# nRF9160.net
KiCad netlist of a schematic drawn in Altium Designer
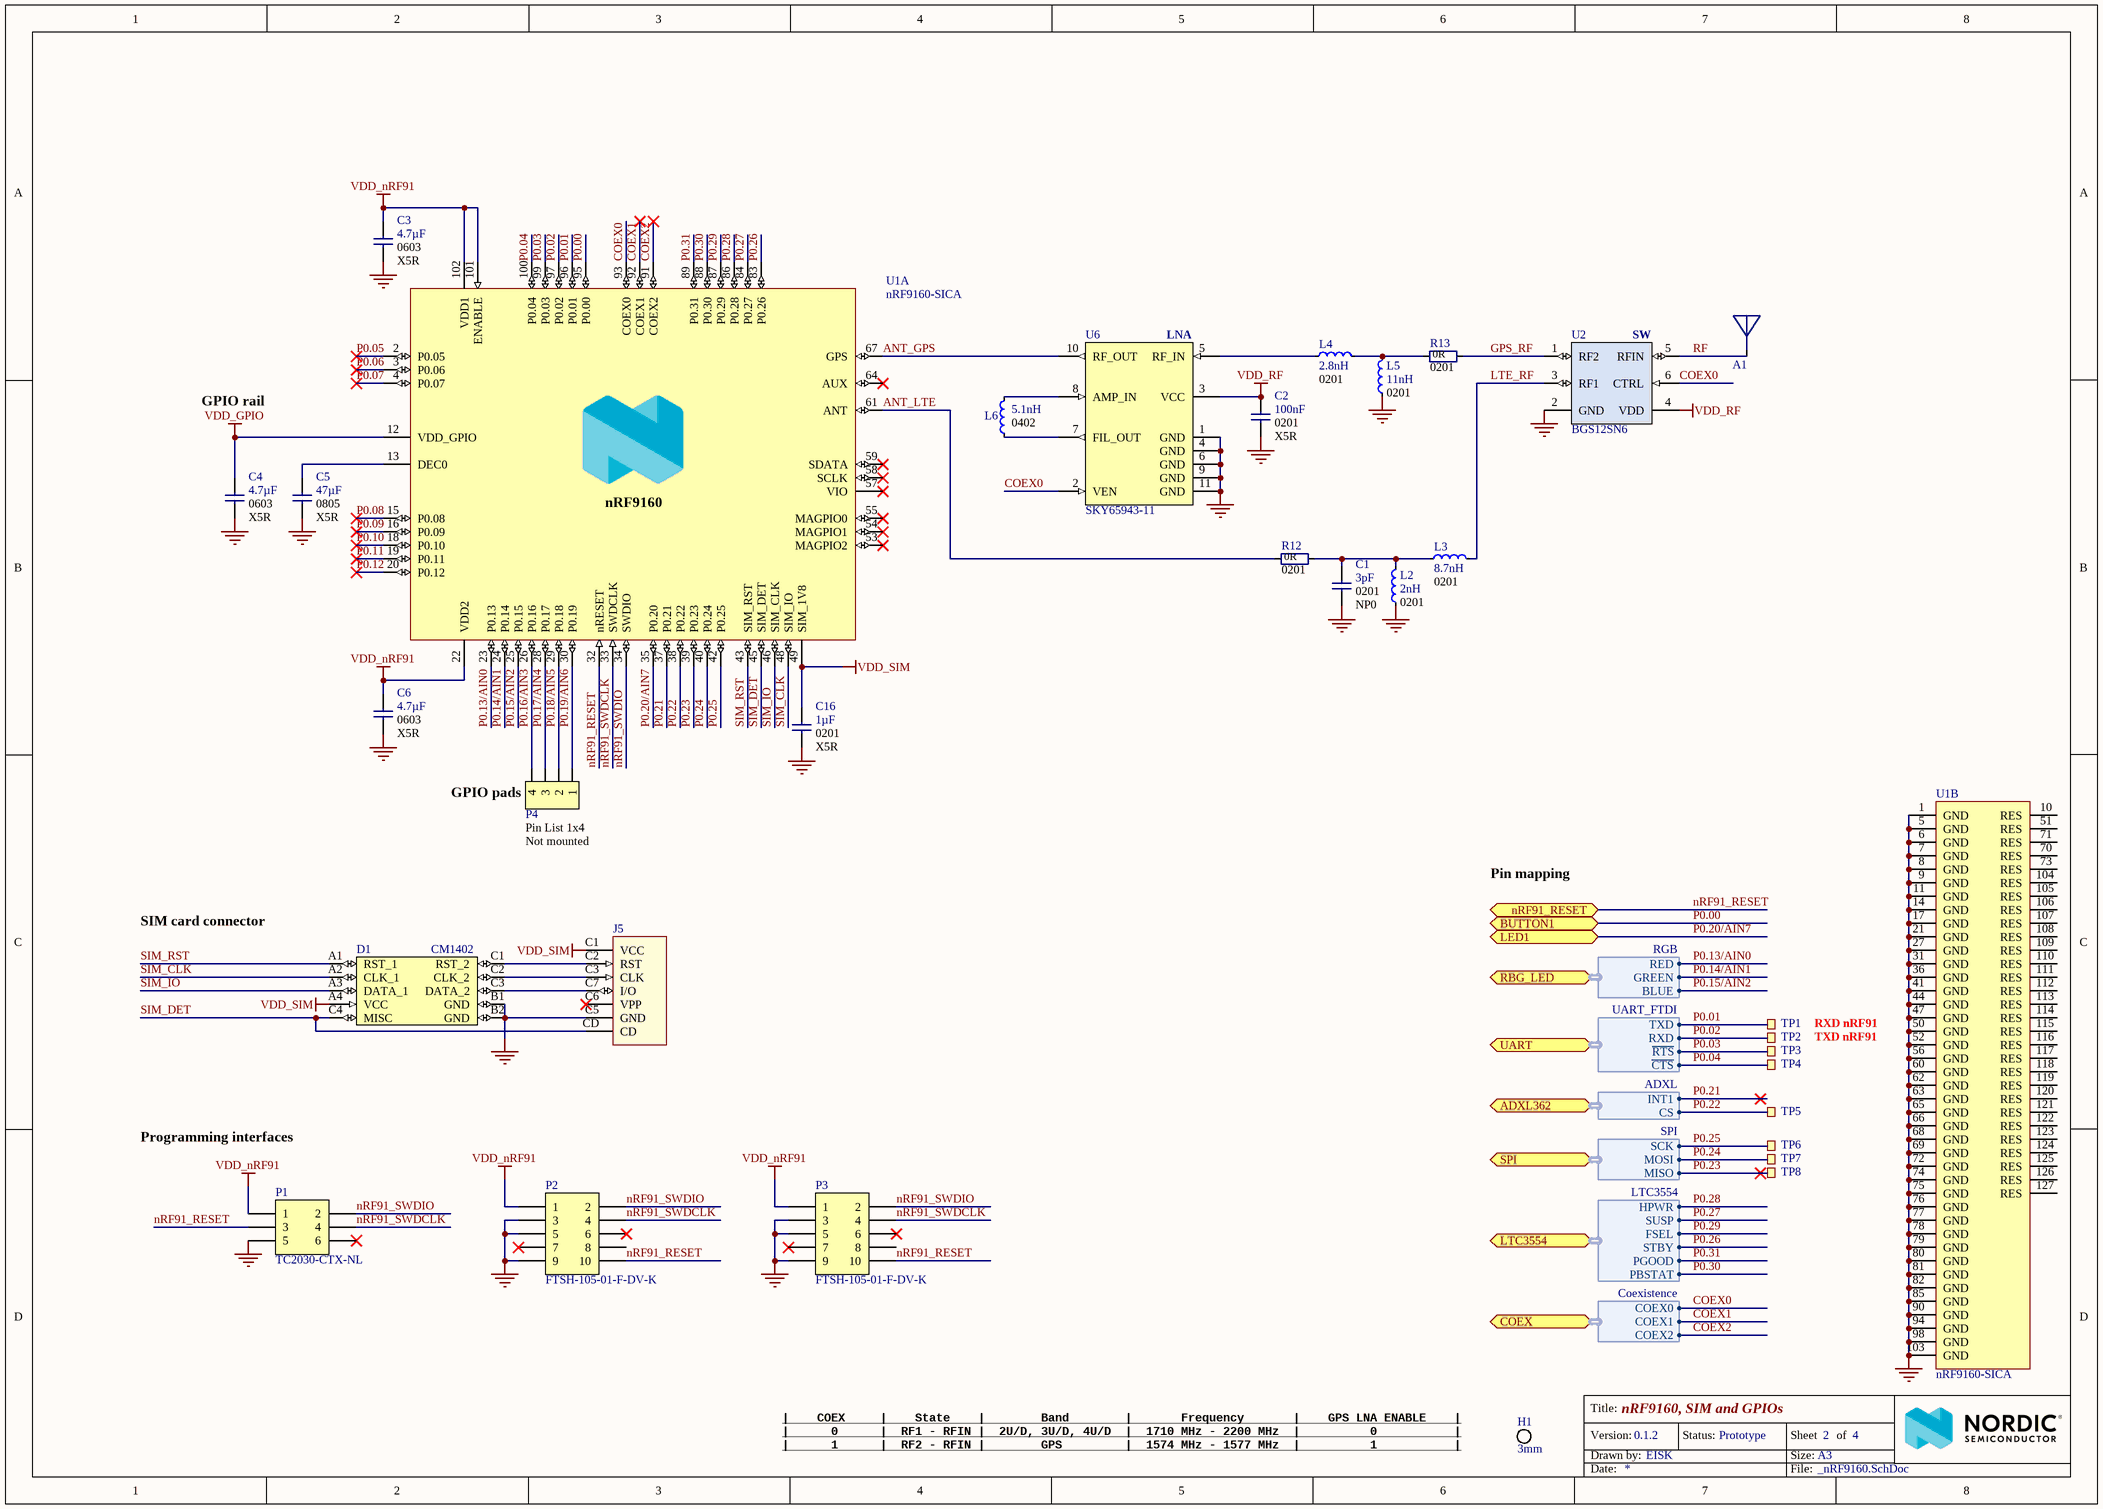
[diagram p0: _nRF9160.SchDoc]

(export (version "E")
  (design (tool "Eeschema 10.0.6"))
  (components
    (comp (ref "A1")
      (value "FR01-S4-250")
      (footprint "FRACTUS_CUBE_mXTEND")
      (description "CUBE mXTEND Antenna Booster (GSM, UMTS, LTE)")
      (fields (field (name "MANUFACTURER") "Fractus Antennas S.L."))
      (libsource (lib "_components") (part "ANT{colon}CUBE_mXTEND"))
    )
    (comp (ref "C1")
      (value "3pF")
      (footprint "CAPC0603X03L_C")
      (description "Capacitor, NP0, ±10%, 10V")
      (fields
        (field (name "FOOTPRINT DOC") "0201")
        (field (name "TEMPCOEFF") "NP0")
        (field (name "PUBLISHER") "Nordic Semiconductor")
      )
      (libsource (lib "_components") (part "CAP{colon}0201"))
    )
    (comp (ref "C2")
      (value "100nF")
      (footprint "CAPC0603X03L_C")
      (description "Capacitor, X5R, ±10%, 10V")
      (fields
        (field (name "FOOTPRINT DOC") "0201")
        (field (name "TEMPCOEFF") "X5R")
        (field (name "PUBLISHER") "Nordic Semiconductor")
      )
      (libsource (lib "_components") (part "CAP{colon}0201"))
    )
    (comp (ref "C3")
      (value "4.7µF")
      (footprint "CAPC1608X06L")
      (description "Capacitor, X5R, ±10%, 6.3V")
      (fields
        (field (name "FOOTPRINT DOC") "0603")
        (field (name "TEMPCOEFF") "X5R")
        (field (name "PUBLISHER") "Nordic Semiconductor")
      )
      (libsource (lib "_components") (part "CAP{colon}0603"))
    )
    (comp (ref "C4")
      (value "4.7µF")
      (footprint "CAPC1608X06L")
      (description "Capacitor, X5R, ±10%, 6.3V")
      (fields
        (field (name "FOOTPRINT DOC") "0603")
        (field (name "TEMPCOEFF") "X5R")
        (field (name "PUBLISHER") "Nordic Semiconductor")
      )
      (libsource (lib "_components") (part "CAP{colon}0603"))
    )
    (comp (ref "C5")
      (value "47µF")
      (footprint "CAPC2012X11L")
      (description "Capacitor, X5R, ±20%, 6.3V")
      (fields
        (field (name "FOOTPRINT DOC") "0805")
        (field (name "TEMPCOEFF") "X5R")
        (field (name "PUBLISHER") "Nordic Semiconductor")
      )
      (libsource (lib "_components") (part "CAP{colon}0805"))
    )
    (comp (ref "C6")
      (value "4.7µF")
      (footprint "CAPC1608X06L")
      (description "Capacitor, X5R, ±10%, 6.3V")
      (fields
        (field (name "FOOTPRINT DOC") "0603")
        (field (name "TEMPCOEFF") "X5R")
        (field (name "PUBLISHER") "Nordic Semiconductor")
      )
      (libsource (lib "_components") (part "CAP{colon}0603"))
    )
    (comp (ref "C16")
      (value "1µF")
      (footprint "CAPC0603X03L_C")
      (description "Capacitor, X5R, ±10%, 10V")
      (fields
        (field (name "FOOTPRINT DOC") "0201")
        (field (name "TEMPCOEFF") "X5R")
        (field (name "PUBLISHER") "Nordic Semiconductor")
      )
      (libsource (lib "_components") (part "CAP{colon}0201"))
    )
    (comp (ref "D1")
      (value "CM1402")
      (footprint "CM1402")
      (description "EMI Network Filter Arrays SIM CARD EMI FILTER WITH ESD PROTECTION")
      (fields
        (field (name "MANUFACTURER") "ON Semiconductor")
        (field (name "MANUFACTURER PART NUMBER") "CM1402-03CP")
        (field (name "PUBLISHER") "Nordic Semiconductor")
      )
      (libsource (lib "_components") (part "CM1402"))
    )
    (comp (ref "H1")
      (value "3mm")
      (footprint "HOLE_NP_3MM")
      (libsource (lib "_components") (part "HOLE{colon}M3"))
    )
    (comp (ref "J5")
      (value "SIM8055-6-1-14-00-A_revA1")
      (footprint "GCT_SIM8055-6-1-14-00-A_revA1")
      (description "Nano SIM Card Connector, Push-Pull Type, 6 Pin, SMT, Profile 1.35mm")
      (fields
        (field (name "MANUFACTURER PART NUMBER") "SIM8055-6-1-14-00-A")
        (field (name "MANUFACTURER") "GCT")
      )
      (libsource (lib "_components") (part "SIM8055-6-1-14-00-A_revA1"))
    )
    (comp (ref "L2")
      (value "2nH")
      (footprint "INDC0603X03L_C")
      (description "Inductor, 350mA, ±3%")
      (fields
        (field (name "MANUFACTURER") "Murata")
        (field (name "FOOTPRINT DOC") "0201")
        (field (name "PUBLISHER") "Nordic Semiconductor")
      )
      (libsource (lib "_components") (part "IND{colon}0201"))
    )
    (comp (ref "L3")
      (value "8.7nH")
      (footprint "INDC0603X03L_C")
      (description "Inductor, 350mA, ±3%")
      (fields
        (field (name "MANUFACTURER") "Murata")
        (field (name "FOOTPRINT DOC") "0201")
        (field (name "PUBLISHER") "Nordic Semiconductor")
      )
      (libsource (lib "_components") (part "IND{colon}0201"))
    )
    (comp (ref "L4")
      (value "2.8nH")
      (footprint "INDC0603X03L_C")
      (description "Inductor, 350mA, ±3%")
      (fields
        (field (name "MANUFACTURER") "Murata")
        (field (name "FOOTPRINT DOC") "0201")
        (field (name "PUBLISHER") "Nordic Semiconductor")
      )
      (libsource (lib "_components") (part "IND{colon}0201"))
    )
    (comp (ref "L5")
      (value "11nH")
      (footprint "INDC0603X03L_C")
      (description "Inductor, 350mA, ±3%")
      (fields
        (field (name "MANUFACTURER") "Murata")
        (field (name "FOOTPRINT DOC") "0201")
        (field (name "PUBLISHER") "Nordic Semiconductor")
      )
      (libsource (lib "_components") (part "IND{colon}0201"))
    )
    (comp (ref "L6")
      (value "5.1nH")
      (footprint "INDC1005X04L_WW")
      (description "Inductor, 600mA, ±0.1nH, 120mΩ, Q=25")
      (fields
        (field (name "PART NUMBER") "L0402-5n1-Wirewound-Murata")
        (field (name "MANUFACTURER") "Murata")
        (field (name "FOOTPRINT DOC") "0402")
        (field (name "PUBLISHER") "Nordic Semiconductor")
      )
      (libsource (lib "_components") (part "IND{colon}Murata"))
    )
    (comp (ref "P1")
      (value "TC2030-CTX-NL")
      (footprint "TC2030-IDC-NLFP")
      (description "CBL PLUG-OF-NAILS 6-PIN")
      (fields
        (field (name "MANUFACTURER") "Tag-Connect LLC")
        (field (name "PUBLISHER") "Nordic Semiconductor")
      )
      (libsource (lib "_components") (part "CONN-2x3_No_BOM"))
    )
    (comp (ref "P2")
      (value "FTSH-105-01-F-DV-K")
      (footprint "HDR_2x5-SMD-1.27mm")
      (description "Connector Header Surface Mount 10 position 0.050\" (1.27mm)")
      (fields (field (name "MANUFACTURER") "Samtec Inc.") (field (name "PUBLISHER") "Nordic Semiconductor"))
      (libsource (lib "_components") (part "Header 2x5 No-BOM"))
    )
    (comp (ref "P3")
      (value "FTSH-105-01-F-DV-K")
      (footprint "HDR_2x5-SMD-1.27mm-K")
      (description "Connector Header Surface Mount 10 position 0.050\" (1.27mm)")
      (fields (field (name "MANUFACTURER") "Samtec Inc.") (field (name "PUBLISHER") "Nordic Semiconductor"))
      (libsource (lib "_components") (part "Header 2x5 Shielded SMD"))
    )
    (comp (ref "P4")
      (value "Pin List 1x4")
      (footprint "LIST_1x4-NC")
      (description "Pin List 1x4, 2.54mm (100mil)")
      (fields (field (name "ASSEMBLY") "Not mounted") (field (name "PUBLISHER") "Nordic Semiconductor"))
      (libsource (lib "_components") (part "CONN-4"))
    )
    (comp (ref "R12")
      (value "0R")
      (footprint "RESC0603X03L_C")
      (fields (field (name "FOOTPRINT DOC") "0201") (field (name "PUBLISHER") "Nordic Semiconductor"))
      (libsource (lib "_components") (part "RES{colon}0201"))
    )
    (comp (ref "R13")
      (value "0R")
      (footprint "RESC0603X03L_C")
      (fields (field (name "FOOTPRINT DOC") "0201") (field (name "PUBLISHER") "Nordic Semiconductor"))
      (libsource (lib "_components") (part "RES{colon}0201"))
    )
    (comp (ref "TP1")
      (value "Ø1.0mm,SMD")
      (footprint "TP_SMD_Ø1.0mm")
      (description "1.0mm circular SMD testpad")
      (fields
        (field (name "MANUFACTURER") "Nordic Semiconductor")
        (field (name "PUBLISHER") "Nordic Semiconductor")
      )
      (libsource (lib "_components") (part "TESTPAD"))
    )
    (comp (ref "TP2")
      (value "Ø1.0mm,SMD")
      (footprint "TP_SMD_Ø1.0mm")
      (description "1.0mm circular SMD testpad")
      (fields
        (field (name "MANUFACTURER") "Nordic Semiconductor")
        (field (name "PUBLISHER") "Nordic Semiconductor")
      )
      (libsource (lib "_components") (part "TESTPAD"))
    )
    (comp (ref "TP3")
      (value "Ø1.0mm,SMD")
      (footprint "TP_SMD_Ø1.0mm")
      (description "1.0mm circular SMD testpad")
      (fields
        (field (name "MANUFACTURER") "Nordic Semiconductor")
        (field (name "PUBLISHER") "Nordic Semiconductor")
      )
      (libsource (lib "_components") (part "TESTPAD"))
    )
    (comp (ref "TP4")
      (value "Ø1.0mm,SMD")
      (footprint "TP_SMD_Ø1.0mm")
      (description "1.0mm circular SMD testpad")
      (fields
        (field (name "MANUFACTURER") "Nordic Semiconductor")
        (field (name "PUBLISHER") "Nordic Semiconductor")
      )
      (libsource (lib "_components") (part "TESTPAD"))
    )
    (comp (ref "TP5")
      (value "Ø1.0mm,SMD")
      (footprint "TP_SMD_Ø1.0mm")
      (description "1.0mm circular SMD testpad")
      (fields
        (field (name "MANUFACTURER") "Nordic Semiconductor")
        (field (name "PUBLISHER") "Nordic Semiconductor")
      )
      (libsource (lib "_components") (part "TESTPAD"))
    )
    (comp (ref "TP6")
      (value "Ø1.0mm,SMD")
      (footprint "TP_SMD_Ø1.0mm")
      (description "1.0mm circular SMD testpad")
      (fields
        (field (name "MANUFACTURER") "Nordic Semiconductor")
        (field (name "PUBLISHER") "Nordic Semiconductor")
      )
      (libsource (lib "_components") (part "TESTPAD"))
    )
    (comp (ref "TP7")
      (value "Ø1.0mm,SMD")
      (footprint "TP_SMD_Ø1.0mm")
      (description "1.0mm circular SMD testpad")
      (fields
        (field (name "MANUFACTURER") "Nordic Semiconductor")
        (field (name "PUBLISHER") "Nordic Semiconductor")
      )
      (libsource (lib "_components") (part "TESTPAD"))
    )
    (comp (ref "TP8")
      (value "Ø1.0mm,SMD")
      (footprint "TP_SMD_Ø1.0mm")
      (description "1.0mm circular SMD testpad")
      (fields
        (field (name "MANUFACTURER") "Nordic Semiconductor")
        (field (name "PUBLISHER") "Nordic Semiconductor")
      )
      (libsource (lib "_components") (part "TESTPAD"))
    )
    (comp (ref "U1")
      (value "nRF9160-SICA")
      (footprint "LGA50P1600X1050X104-161N")
      (description "Low power System-in-Package with integrated LTE-M/NB-IoT modem and GPS")
      (fields
        (field (name "MANUFACTURER") "Nordic Semiconductor")
        (field (name "PUBLISHER") "Nordic Semiconductor")
      )
      (libsource (lib "_components") (part "nRF9160_SICA"))
    )
    (comp (ref "U2")
      (value "BGS12SN6")
      (footprint "PG-TSNP-6-2")
      (description "Wideband RF SPDT Switch")
      (fields (field (name "MANUFACTURER") "Infineon Technologies"))
      (libsource (lib "_components") (part "BGS12SN6"))
    )
    (comp (ref "U6")
      (value "SKY65943-11")
      (footprint "SKY6594311")
      (description "GNSS Low-Noise Amplifier Front-End Module with Integrated Pre-Filter and Post-Filter")
      (fields (field (name "MANUFACTURER") "Skyworks") (field (name "PUBLISHER") "Nordic Semiconductor"))
      (libsource (lib "_components") (part "SKY65943-11"))
    )
  )
  (nets
    (net (code "7") (name "/ANT_GPS") (class "Default")
      (node (ref "U1") (pin "67") (pinfunction "GPS_67") (pintype "bidirectional"))
      (node (ref "U6") (pin "10") (pinfunction "RF_OUT_10") (pintype "output"))
    )
    (net (code "8") (name "/ANT_LTE") (class "Default")
      (node (ref "R12") (pin "1") (pinfunction "1_1") (pintype "passive"))
      (node (ref "U1") (pin "61") (pinfunction "ANT_61") (pintype "bidirectional"))
    )
    (net (code "9") (name "/COEX0") (class "Default")
      (node (ref "U1") (pin "93") (pinfunction "COEX0_93") (pintype "bidirectional"))
      (node (ref "U2") (pin "6") (pinfunction "CTRL_6") (pintype "input"))
      (node (ref "U6") (pin "2") (pinfunction "VEN_2") (pintype "input"))
    )
    (net (code "10") (name "/COEX1") (class "Default")
      (node (ref "U1") (pin "92") (pinfunction "COEX1_92") (pintype "bidirectional+no_connect"))
    )
    (net (code "11") (name "/COEX2") (class "Default")
      (node (ref "U1") (pin "91") (pinfunction "COEX2_91") (pintype "bidirectional+no_connect"))
    )
    (net (code "12") (name "/GPS_RF") (class "Default")
      (node (ref "R13") (pin "2") (pinfunction "2_2") (pintype "passive"))
      (node (ref "U2") (pin "1") (pinfunction "RF2_1") (pintype "bidirectional"))
    )
    (net (code "13") (name "/LTE_RF") (class "Default")
      (node (ref "L3") (pin "2") (pinfunction "2_2") (pintype "passive"))
      (node (ref "U2") (pin "3") (pinfunction "RF1_3") (pintype "bidirectional"))
    )
    (net (code "14") (name "/P0.00") (class "Default")
      (node (ref "U1") (pin "95") (pinfunction "P0.00_95") (pintype "bidirectional"))
    )
    (net (code "15") (name "/P0.01") (class "Default")
      (node (ref "TP1") (pin "1") (pinfunction "1_1") (pintype "passive"))
      (node (ref "U1") (pin "96") (pinfunction "P0.01_96") (pintype "bidirectional"))
    )
    (net (code "16") (name "/P0.02") (class "Default")
      (node (ref "TP2") (pin "1") (pinfunction "1_1") (pintype "passive"))
      (node (ref "U1") (pin "97") (pinfunction "P0.02_97") (pintype "bidirectional"))
    )
    (net (code "17") (name "/P0.03") (class "Default")
      (node (ref "TP3") (pin "1") (pinfunction "1_1") (pintype "passive"))
      (node (ref "U1") (pin "99") (pinfunction "P0.03_99") (pintype "bidirectional"))
    )
    (net (code "18") (name "/P0.04") (class "Default")
      (node (ref "TP4") (pin "1") (pinfunction "1_1") (pintype "passive"))
      (node (ref "U1") (pin "100") (pinfunction "P0.04_100") (pintype "bidirectional"))
    )
    (net (code "19") (name "/P0.05") (class "Default")
      (node (ref "U1") (pin "2") (pinfunction "P0.05_2") (pintype "bidirectional+no_connect"))
    )
    (net (code "20") (name "/P0.06") (class "Default")
      (node (ref "U1") (pin "3") (pinfunction "P0.06_3") (pintype "bidirectional+no_connect"))
    )
    (net (code "21") (name "/P0.07") (class "Default")
      (node (ref "U1") (pin "4") (pinfunction "P0.07_4") (pintype "bidirectional+no_connect"))
    )
    (net (code "22") (name "/P0.08") (class "Default")
      (node (ref "U1") (pin "15") (pinfunction "P0.08_15") (pintype "bidirectional+no_connect"))
    )
    (net (code "23") (name "/P0.09") (class "Default")
      (node (ref "U1") (pin "16") (pinfunction "P0.09_16") (pintype "bidirectional+no_connect"))
    )
    (net (code "24") (name "/P0.10") (class "Default")
      (node (ref "U1") (pin "18") (pinfunction "P0.10_18") (pintype "bidirectional+no_connect"))
    )
    (net (code "25") (name "/P0.11") (class "Default")
      (node (ref "U1") (pin "19") (pinfunction "P0.11_19") (pintype "bidirectional+no_connect"))
    )
    (net (code "26") (name "/P0.12") (class "Default")
      (node (ref "U1") (pin "20") (pinfunction "P0.12_20") (pintype "bidirectional+no_connect"))
    )
    (net (code "27") (name "/P0.13{slash}AIN0") (class "Default")
      (node (ref "U1") (pin "23") (pinfunction "P0.13_23") (pintype "bidirectional"))
    )
    (net (code "28") (name "/P0.14{slash}AIN1") (class "Default")
      (node (ref "U1") (pin "24") (pinfunction "P0.14_24") (pintype "bidirectional"))
    )
    (net (code "29") (name "/P0.15{slash}AIN2") (class "Default")
      (node (ref "U1") (pin "25") (pinfunction "P0.15_25") (pintype "bidirectional"))
    )
    (net (code "30") (name "/P0.16{slash}AIN3") (class "Default")
      (node (ref "P4") (pin "4") (pinfunction "4_4") (pintype "passive"))
      (node (ref "U1") (pin "26") (pinfunction "P0.16_26") (pintype "bidirectional"))
    )
    (net (code "31") (name "/P0.17{slash}AIN4") (class "Default")
      (node (ref "P4") (pin "3") (pinfunction "3_3") (pintype "passive"))
      (node (ref "U1") (pin "28") (pinfunction "P0.17_28") (pintype "bidirectional"))
    )
    (net (code "32") (name "/P0.18{slash}AIN5") (class "Default")
      (node (ref "P4") (pin "2") (pinfunction "2_2") (pintype "passive"))
      (node (ref "U1") (pin "29") (pinfunction "P0.18_29") (pintype "bidirectional"))
    )
    (net (code "33") (name "/P0.19{slash}AIN6") (class "Default")
      (node (ref "P4") (pin "1") (pinfunction "1_1") (pintype "passive"))
      (node (ref "U1") (pin "30") (pinfunction "P0.19_30") (pintype "bidirectional"))
    )
    (net (code "34") (name "/P0.20{slash}AIN7") (class "Default")
      (node (ref "U1") (pin "35") (pinfunction "P0.20_35") (pintype "bidirectional"))
    )
    (net (code "35") (name "/P0.21") (class "Default")
      (node (ref "U1") (pin "37") (pinfunction "P0.21_37") (pintype "bidirectional"))
    )
    (net (code "36") (name "/P0.22") (class "Default")
      (node (ref "TP5") (pin "1") (pinfunction "1_1") (pintype "passive"))
      (node (ref "U1") (pin "38") (pinfunction "P0.22_38") (pintype "bidirectional"))
    )
    (net (code "37") (name "/P0.23") (class "Default")
      (node (ref "TP8") (pin "1") (pinfunction "1_1") (pintype "passive"))
      (node (ref "U1") (pin "39") (pinfunction "P0.23_39") (pintype "bidirectional"))
    )
    (net (code "38") (name "/P0.24") (class "Default")
      (node (ref "TP7") (pin "1") (pinfunction "1_1") (pintype "passive"))
      (node (ref "U1") (pin "40") (pinfunction "P0.24_40") (pintype "bidirectional"))
    )
    (net (code "39") (name "/P0.25") (class "Default")
      (node (ref "TP6") (pin "1") (pinfunction "1_1") (pintype "passive"))
      (node (ref "U1") (pin "42") (pinfunction "P0.25_42") (pintype "bidirectional"))
    )
    (net (code "40") (name "/P0.26") (class "Default")
      (node (ref "U1") (pin "83") (pinfunction "P0.26_83") (pintype "bidirectional"))
    )
    (net (code "41") (name "/P0.27") (class "Default")
      (node (ref "U1") (pin "84") (pinfunction "P0.27_84") (pintype "bidirectional"))
    )
    (net (code "42") (name "/P0.28") (class "Default")
      (node (ref "U1") (pin "86") (pinfunction "P0.28_86") (pintype "bidirectional"))
    )
    (net (code "43") (name "/P0.29") (class "Default")
      (node (ref "U1") (pin "87") (pinfunction "P0.29_87") (pintype "bidirectional"))
    )
    (net (code "44") (name "/P0.30") (class "Default")
      (node (ref "U1") (pin "88") (pinfunction "P0.30_88") (pintype "bidirectional"))
    )
    (net (code "45") (name "/P0.31") (class "Default")
      (node (ref "U1") (pin "89") (pinfunction "P0.31_89") (pintype "bidirectional"))
    )
    (net (code "46") (name "/RF") (class "Default")
      (node (ref "A1") (pin "1") (pinfunction "1_1") (pintype "passive"))
      (node (ref "U2") (pin "5") (pinfunction "RFIN_5") (pintype "bidirectional"))
    )
    (net (code "47") (name "/SIM_CLK") (class "Default")
      (node (ref "D1") (pin "A2") (pinfunction "CLK_1_A2") (pintype "bidirectional"))
      (node (ref "U1") (pin "48") (pinfunction "SIM_IO_48") (pintype "bidirectional"))
    )
    (net (code "48") (name "/SIM_DET") (class "Default")
      (node (ref "D1") (pin "C4") (pinfunction "MISC_C4") (pintype "bidirectional"))
      (node (ref "J5") (pin "CD") (pinfunction "CD_CD") (pintype "passive"))
      (node (ref "U1") (pin "45") (pinfunction "SIM_DET_45") (pintype "bidirectional"))
    )
    (net (code "49") (name "/SIM_IO") (class "Default")
      (node (ref "D1") (pin "A3") (pinfunction "DATA_1_A3") (pintype "bidirectional"))
      (node (ref "U1") (pin "46") (pinfunction "SIM_CLK_46") (pintype "bidirectional"))
    )
    (net (code "50") (name "/SIM_RST") (class "Default")
      (node (ref "D1") (pin "A1") (pinfunction "RST_1_A1") (pintype "bidirectional"))
      (node (ref "U1") (pin "43") (pinfunction "SIM_RST_43") (pintype "bidirectional"))
    )
    (net (code "51") (name "/nRF91_RESET") (class "Default")
      (node (ref "P1") (pin "3") (pinfunction "3_3") (pintype "passive"))
      (node (ref "P2") (pin "10") (pinfunction "10_10") (pintype "passive"))
      (node (ref "P3") (pin "10") (pinfunction "10_10") (pintype "passive"))
      (node (ref "U1") (pin "32") (pinfunction "nRESET_32") (pintype "input"))
    )
    (net (code "52") (name "/nRF91_SWDCLK") (class "Default")
      (node (ref "P1") (pin "4") (pinfunction "4_4") (pintype "passive"))
      (node (ref "P2") (pin "4") (pinfunction "4_4") (pintype "passive"))
      (node (ref "P3") (pin "4") (pinfunction "4_4") (pintype "passive"))
      (node (ref "U1") (pin "33") (pinfunction "SWDCLK_33") (pintype "input"))
    )
    (net (code "53") (name "/nRF91_SWDIO") (class "Default")
      (node (ref "P1") (pin "2") (pinfunction "2_2") (pintype "passive"))
      (node (ref "P2") (pin "2") (pinfunction "2_2") (pintype "passive"))
      (node (ref "P3") (pin "2") (pinfunction "2_2") (pintype "passive"))
      (node (ref "U1") (pin "34") (pinfunction "SWDIO_34") (pintype "bidirectional"))
    )
    (net (code "60") (name "GND") (class "Default")
      (node (ref "C1") (pin "2") (pinfunction "2_2") (pintype "passive"))
      (node (ref "C16") (pin "2") (pinfunction "2_2") (pintype "passive"))
      (node (ref "C2") (pin "2") (pinfunction "2_2") (pintype "passive"))
      (node (ref "C3") (pin "2") (pinfunction "2_2") (pintype "passive"))
      (node (ref "C4") (pin "2") (pinfunction "2_2") (pintype "passive"))
      (node (ref "C5") (pin "2") (pinfunction "2_2") (pintype "passive"))
      (node (ref "C6") (pin "2") (pinfunction "2_2") (pintype "passive"))
      (node (ref "D1") (pin "B1") (pinfunction "GND_B1") (pintype "bidirectional"))
      (node (ref "D1") (pin "B2") (pinfunction "GND_B2") (pintype "bidirectional"))
      (node (ref "J5") (pin "C5") (pinfunction "GND_C5") (pintype "power_in"))
      (node (ref "L2") (pin "1") (pinfunction "1_1") (pintype "passive"))
      (node (ref "L5") (pin "1") (pinfunction "1_1") (pintype "passive"))
      (node (ref "P1") (pin "5") (pinfunction "5_5") (pintype "passive"))
      (node (ref "P2") (pin "3") (pinfunction "3_3") (pintype "passive"))
      (node (ref "P2") (pin "5") (pinfunction "5_5") (pintype "passive"))
      (node (ref "P2") (pin "9") (pinfunction "9_9") (pintype "passive"))
      (node (ref "P3") (pin "3") (pinfunction "3_3") (pintype "passive"))
      (node (ref "P3") (pin "5") (pinfunction "5_5") (pintype "passive"))
      (node (ref "P3") (pin "9") (pinfunction "9_9") (pintype "passive"))
      (node (ref "U1") (pin "1") (pinfunction "GND_1") (pintype "power_in"))
      (node (ref "U1") (pin "103") (pinfunction "GND_103") (pintype "power_in"))
      (node (ref "U1") (pin "11") (pinfunction "GND_11") (pintype "passive"))
      (node (ref "U1") (pin "14") (pinfunction "GND_14") (pintype "power_in"))
      (node (ref "U1") (pin "17") (pinfunction "GND_17") (pintype "power_in"))
      (node (ref "U1") (pin "21") (pinfunction "GND_21") (pintype "power_in"))
      (node (ref "U1") (pin "27") (pinfunction "GND_27") (pintype "power_in"))
      (node (ref "U1") (pin "31") (pinfunction "GND_31") (pintype "power_in"))
      (node (ref "U1") (pin "36") (pinfunction "GND_36") (pintype "power_in"))
      (node (ref "U1") (pin "41") (pinfunction "GND_41") (pintype "power_in"))
      (node (ref "U1") (pin "44") (pinfunction "GND_44") (pintype "power_in"))
      (node (ref "U1") (pin "47") (pinfunction "GND_47") (pintype "power_in"))
      (node (ref "U1") (pin "5") (pinfunction "GND_5") (pintype "power_in"))
      (node (ref "U1") (pin "50") (pinfunction "GND_50") (pintype "power_in"))
      (node (ref "U1") (pin "52") (pinfunction "GND_52") (pintype "power_in"))
      (node (ref "U1") (pin "56") (pinfunction "GND_56") (pintype "power_in"))
      (node (ref "U1") (pin "6") (pinfunction "GND_6") (pintype "passive"))
      (node (ref "U1") (pin "60") (pinfunction "GND_60") (pintype "power_in"))
      (node (ref "U1") (pin "62") (pinfunction "GND_62") (pintype "power_in"))
      (node (ref "U1") (pin "63") (pinfunction "GND_63") (pintype "power_in"))
      (node (ref "U1") (pin "65") (pinfunction "GND_65") (pintype "power_in"))
      (node (ref "U1") (pin "66") (pinfunction "GND_66") (pintype "power_in"))
      (node (ref "U1") (pin "68") (pinfunction "GND_68") (pintype "passive"))
      (node (ref "U1") (pin "69") (pinfunction "GND_69") (pintype "passive"))
      (node (ref "U1") (pin "7") (pinfunction "GND_7") (pintype "passive"))
      (node (ref "U1") (pin "72") (pinfunction "GND_72") (pintype "power_in"))
      (node (ref "U1") (pin "74") (pinfunction "GND_74") (pintype "power_in"))
      (node (ref "U1") (pin "75") (pinfunction "GND_75") (pintype "power_in"))
      (node (ref "U1") (pin "76") (pinfunction "GND_76") (pintype "power_in"))
      (node (ref "U1") (pin "77") (pinfunction "GND_77") (pintype "power_in"))
      (node (ref "U1") (pin "78") (pinfunction "GND_78") (pintype "power_in"))
      (node (ref "U1") (pin "79") (pinfunction "GND_79") (pintype "power_in"))
      (node (ref "U1") (pin "8") (pinfunction "GND_8") (pintype "passive"))
      (node (ref "U1") (pin "80") (pinfunction "GND_80") (pintype "power_in"))
      (node (ref "U1") (pin "81") (pinfunction "GND_81") (pintype "power_in"))
      (node (ref "U1") (pin "82") (pinfunction "GND_82") (pintype "power_in"))
      (node (ref "U1") (pin "85") (pinfunction "GND_85") (pintype "power_in"))
      (node (ref "U1") (pin "9") (pinfunction "GND_9") (pintype "power_in"))
      (node (ref "U1") (pin "90") (pinfunction "GND_90") (pintype "power_in"))
      (node (ref "U1") (pin "94") (pinfunction "GND_94") (pintype "power_in"))
      (node (ref "U1") (pin "98") (pinfunction "GND_98") (pintype "power_in"))
      (node (ref "U2") (pin "2") (pinfunction "GND_2") (pintype "power_in"))
      (node (ref "U6") (pin "1") (pinfunction "GND_1") (pintype "power_in"))
      (node (ref "U6") (pin "11") (pinfunction "GND_11") (pintype "power_in"))
      (node (ref "U6") (pin "4") (pinfunction "GND_4") (pintype "power_in"))
      (node (ref "U6") (pin "6") (pinfunction "GND_6") (pintype "power_in"))
      (node (ref "U6") (pin "9") (pinfunction "GND_9") (pintype "power_in"))
    )
    (net (code "61") (name "Net-(C1-Pad1)") (class "Default")
      (node (ref "C1") (pin "1") (pinfunction "1_1") (pintype "passive"))
      (node (ref "L2") (pin "2") (pinfunction "2_2") (pintype "passive"))
      (node (ref "L3") (pin "1") (pinfunction "1_1") (pintype "passive"))
      (node (ref "R12") (pin "2") (pinfunction "2_2") (pintype "passive"))
    )
    (net (code "62") (name "Net-(D1-CLK_2)") (class "Default")
      (node (ref "D1") (pin "C2") (pinfunction "CLK_2_C2") (pintype "bidirectional"))
      (node (ref "J5") (pin "C3") (pinfunction "CLK_C3") (pintype "input"))
    )
    (net (code "63") (name "Net-(D1-DATA_2)") (class "Default")
      (node (ref "D1") (pin "C3") (pinfunction "DATA_2_C3") (pintype "bidirectional"))
      (node (ref "J5") (pin "C7") (pinfunction "I/O_C7") (pintype "bidirectional"))
    )
    (net (code "64") (name "Net-(D1-RST_2)") (class "Default")
      (node (ref "D1") (pin "C1") (pinfunction "RST_2_C1") (pintype "bidirectional"))
      (node (ref "J5") (pin "C2") (pinfunction "RST_C2") (pintype "input"))
    )
    (net (code "65") (name "Net-(L4-Pad2)") (class "Default")
      (node (ref "L4") (pin "2") (pinfunction "2_2") (pintype "passive"))
      (node (ref "L5") (pin "2") (pinfunction "2_2") (pintype "passive"))
      (node (ref "R13") (pin "1") (pinfunction "1_1") (pintype "passive"))
    )
    (net (code "66") (name "Net-(U1A-DEC0)") (class "Default")
      (node (ref "C5") (pin "1") (pinfunction "1_1") (pintype "passive"))
      (node (ref "U1") (pin "13") (pinfunction "DEC0_13") (pintype "power_in"))
    )
    (net (code "67") (name "Net-(U6-AMP_IN)") (class "Default")
      (node (ref "L6") (pin "2") (pinfunction "2_2") (pintype "passive"))
      (node (ref "U6") (pin "8") (pinfunction "AMP_IN_8") (pintype "input"))
    )
    (net (code "68") (name "Net-(U6-FIL_OUT)") (class "Default")
      (node (ref "L6") (pin "1") (pinfunction "1_1") (pintype "passive"))
      (node (ref "U6") (pin "7") (pinfunction "FIL_OUT_7") (pintype "output"))
    )
    (net (code "69") (name "Net-(U6-RF_IN)") (class "Default")
      (node (ref "L4") (pin "1") (pinfunction "1_1") (pintype "passive"))
      (node (ref "U6") (pin "5") (pinfunction "RF_IN_5") (pintype "input"))
    )
    (net (code "70") (name "VDD_GPIO") (class "Default")
      (node (ref "C4") (pin "1") (pinfunction "1_1") (pintype "passive"))
      (node (ref "U1") (pin "12") (pinfunction "VDD_GPIO_12") (pintype "power_in"))
    )
    (net (code "71") (name "VDD_RF") (class "Default")
      (node (ref "C2") (pin "1") (pinfunction "1_1") (pintype "passive"))
      (node (ref "U2") (pin "4") (pinfunction "VDD_4") (pintype "power_in"))
      (node (ref "U6") (pin "3") (pinfunction "VCC_3") (pintype "power_in"))
    )
    (net (code "72") (name "VDD_SIM") (class "Default")
      (node (ref "C16") (pin "1") (pinfunction "1_1") (pintype "passive"))
      (node (ref "D1") (pin "A4") (pinfunction "VCC_A4") (pintype "input"))
      (node (ref "J5") (pin "C1") (pinfunction "VCC_C1") (pintype "power_in"))
      (node (ref "U1") (pin "49") (pinfunction "SIM_1V8_49") (pintype "power_in"))
    )
    (net (code "73") (name "VDD_nRF91") (class "Default")
      (node (ref "C3") (pin "1") (pinfunction "1_1") (pintype "passive"))
      (node (ref "C6") (pin "1") (pinfunction "1_1") (pintype "passive"))
      (node (ref "P1") (pin "1") (pinfunction "1_1") (pintype "passive"))
      (node (ref "P2") (pin "1") (pinfunction "1_1") (pintype "passive"))
      (node (ref "P3") (pin "1") (pinfunction "1_1") (pintype "passive"))
      (node (ref "U1") (pin "101") (pinfunction "ENABLE_101") (pintype "input"))
      (node (ref "U1") (pin "102") (pinfunction "VDD1_102") (pintype "power_in"))
      (node (ref "U1") (pin "22") (pinfunction "VDD2_22") (pintype "power_in"))
    )
    (net (code "74") (name "unconnected-(J5-VPP-PadC6)") (class "Default")
      (node (ref "J5") (pin "C6") (pinfunction "VPP_C6") (pintype "power_in+no_connect"))
    )
    (net (code "75") (name "unconnected-(P1-Pad6)") (class "Default")
      (node (ref "P1") (pin "6") (pinfunction "6_6") (pintype "passive+no_connect"))
    )
    (net (code "76") (name "unconnected-(P2-Pad6)") (class "Default")
      (node (ref "P2") (pin "6") (pinfunction "6_6") (pintype "passive+no_connect"))
    )
    (net (code "77") (name "unconnected-(P2-Pad7)") (class "Default")
      (node (ref "P2") (pin "7") (pinfunction "7_7") (pintype "passive+no_connect"))
    )
    (net (code "78") (name "unconnected-(P2-Pad8)") (class "Default")
      (node (ref "P2") (pin "8") (pinfunction "8_8") (pintype "passive"))
    )
    (net (code "79") (name "unconnected-(P3-Pad6)") (class "Default")
      (node (ref "P3") (pin "6") (pinfunction "6_6") (pintype "passive+no_connect"))
    )
    (net (code "80") (name "unconnected-(P3-Pad7)") (class "Default")
      (node (ref "P3") (pin "7") (pinfunction "7_7") (pintype "passive+no_connect"))
    )
    (net (code "81") (name "unconnected-(P3-Pad8)") (class "Default")
      (node (ref "P3") (pin "8") (pinfunction "8_8") (pintype "passive"))
    )
    (net (code "82") (name "unconnected-(U1A-AUX-Pad64)") (class "Default")
      (node (ref "U1") (pin "64") (pinfunction "AUX_64") (pintype "bidirectional+no_connect"))
    )
    (net (code "83") (name "unconnected-(U1A-MAGPIO0-Pad55)") (class "Default")
      (node (ref "U1") (pin "55") (pinfunction "MAGPIO0_55") (pintype "bidirectional+no_connect"))
    )
    (net (code "84") (name "unconnected-(U1A-MAGPIO1-Pad54)") (class "Default")
      (node (ref "U1") (pin "54") (pinfunction "MAGPIO1_54") (pintype "bidirectional+no_connect"))
    )
    (net (code "85") (name "unconnected-(U1A-MAGPIO2-Pad53)") (class "Default")
      (node (ref "U1") (pin "53") (pinfunction "MAGPIO2_53") (pintype "bidirectional+no_connect"))
    )
    (net (code "86") (name "unconnected-(U1A-SCLK-Pad58)") (class "Default")
      (node (ref "U1") (pin "58") (pinfunction "SCLK_58") (pintype "bidirectional+no_connect"))
    )
    (net (code "87") (name "unconnected-(U1A-SDATA-Pad59)") (class "Default")
      (node (ref "U1") (pin "59") (pinfunction "SDATA_59") (pintype "bidirectional+no_connect"))
    )
    (net (code "88") (name "unconnected-(U1A-VIO-Pad57)") (class "Default")
      (node (ref "U1") (pin "57") (pinfunction "VIO_57") (pintype "power_in+no_connect"))
    )
    (net (code "89") (name "unconnected-(U1B-RES-Pad10)") (class "Default")
      (node (ref "U1") (pin "10") (pinfunction "RES_10") (pintype "passive"))
    )
    (net (code "90") (name "unconnected-(U1B-RES-Pad51)") (class "Default")
      (node (ref "U1") (pin "51") (pinfunction "RES_51") (pintype "passive"))
    )
    (net (code "91") (name "unconnected-(U1B-RES-Pad70)") (class "Default")
      (node (ref "U1") (pin "70") (pinfunction "RES_70") (pintype "passive"))
    )
    (net (code "92") (name "unconnected-(U1B-RES-Pad71)") (class "Default")
      (node (ref "U1") (pin "71") (pinfunction "RES_71") (pintype "passive"))
    )
    (net (code "93") (name "unconnected-(U1B-RES-Pad73)") (class "Default")
      (node (ref "U1") (pin "73") (pinfunction "RES_73") (pintype "passive"))
    )
    (net (code "94") (name "unconnected-(U1B-RES-Pad104)") (class "Default")
      (node (ref "U1") (pin "104") (pinfunction "RES_104") (pintype "passive"))
    )
    (net (code "95") (name "unconnected-(U1B-RES-Pad105)") (class "Default")
      (node (ref "U1") (pin "105") (pinfunction "RES_105") (pintype "passive"))
    )
    (net (code "96") (name "unconnected-(U1B-RES-Pad106)") (class "Default")
      (node (ref "U1") (pin "106") (pinfunction "RES_106") (pintype "passive"))
    )
    (net (code "97") (name "unconnected-(U1B-RES-Pad107)") (class "Default")
      (node (ref "U1") (pin "107") (pinfunction "RES_107") (pintype "passive"))
    )
    (net (code "98") (name "unconnected-(U1B-RES-Pad108)") (class "Default")
      (node (ref "U1") (pin "108") (pinfunction "RES_108") (pintype "passive"))
    )
    (net (code "99") (name "unconnected-(U1B-RES-Pad109)") (class "Default")
      (node (ref "U1") (pin "109") (pinfunction "RES_109") (pintype "passive"))
    )
    (net (code "100") (name "unconnected-(U1B-RES-Pad110)") (class "Default")
      (node (ref "U1") (pin "110") (pinfunction "RES_110") (pintype "passive"))
    )
    (net (code "101") (name "unconnected-(U1B-RES-Pad111)") (class "Default")
      (node (ref "U1") (pin "111") (pinfunction "RES_111") (pintype "passive"))
    )
    (net (code "102") (name "unconnected-(U1B-RES-Pad112)") (class "Default")
      (node (ref "U1") (pin "112") (pinfunction "RES_112") (pintype "passive"))
    )
    (net (code "103") (name "unconnected-(U1B-RES-Pad113)") (class "Default")
      (node (ref "U1") (pin "113") (pinfunction "RES_113") (pintype "passive"))
    )
    (net (code "104") (name "unconnected-(U1B-RES-Pad114)") (class "Default")
      (node (ref "U1") (pin "114") (pinfunction "RES_114") (pintype "passive"))
    )
    (net (code "105") (name "unconnected-(U1B-RES-Pad115)") (class "Default")
      (node (ref "U1") (pin "115") (pinfunction "RES_115") (pintype "passive"))
    )
    (net (code "106") (name "unconnected-(U1B-RES-Pad116)") (class "Default")
      (node (ref "U1") (pin "116") (pinfunction "RES_116") (pintype "passive"))
    )
    (net (code "107") (name "unconnected-(U1B-RES-Pad117)") (class "Default")
      (node (ref "U1") (pin "117") (pinfunction "RES_117") (pintype "passive"))
    )
    (net (code "108") (name "unconnected-(U1B-RES-Pad118)") (class "Default")
      (node (ref "U1") (pin "118") (pinfunction "RES_118") (pintype "passive"))
    )
    (net (code "109") (name "unconnected-(U1B-RES-Pad119)") (class "Default")
      (node (ref "U1") (pin "119") (pinfunction "RES_119") (pintype "passive"))
    )
    (net (code "110") (name "unconnected-(U1B-RES-Pad120)") (class "Default")
      (node (ref "U1") (pin "120") (pinfunction "RES_120") (pintype "passive"))
    )
    (net (code "111") (name "unconnected-(U1B-RES-Pad121)") (class "Default")
      (node (ref "U1") (pin "121") (pinfunction "RES_121") (pintype "passive"))
    )
    (net (code "112") (name "unconnected-(U1B-RES-Pad122)") (class "Default")
      (node (ref "U1") (pin "122") (pinfunction "RES_122") (pintype "passive"))
    )
    (net (code "113") (name "unconnected-(U1B-RES-Pad123)") (class "Default")
      (node (ref "U1") (pin "123") (pinfunction "RES_123") (pintype "passive"))
    )
    (net (code "114") (name "unconnected-(U1B-RES-Pad124)") (class "Default")
      (node (ref "U1") (pin "124") (pinfunction "RES_124") (pintype "passive"))
    )
    (net (code "115") (name "unconnected-(U1B-RES-Pad125)") (class "Default")
      (node (ref "U1") (pin "125") (pinfunction "RES_125") (pintype "passive"))
    )
    (net (code "116") (name "unconnected-(U1B-RES-Pad126)") (class "Default")
      (node (ref "U1") (pin "126") (pinfunction "RES_126") (pintype "passive"))
    )
    (net (code "117") (name "unconnected-(U1B-RES-Pad127)") (class "Default")
      (node (ref "U1") (pin "127") (pinfunction "RES_127") (pintype "passive"))
    )
  )
)
